# USB_Controller.net
KiCad netlist of a schematic drawn in Altium Designer
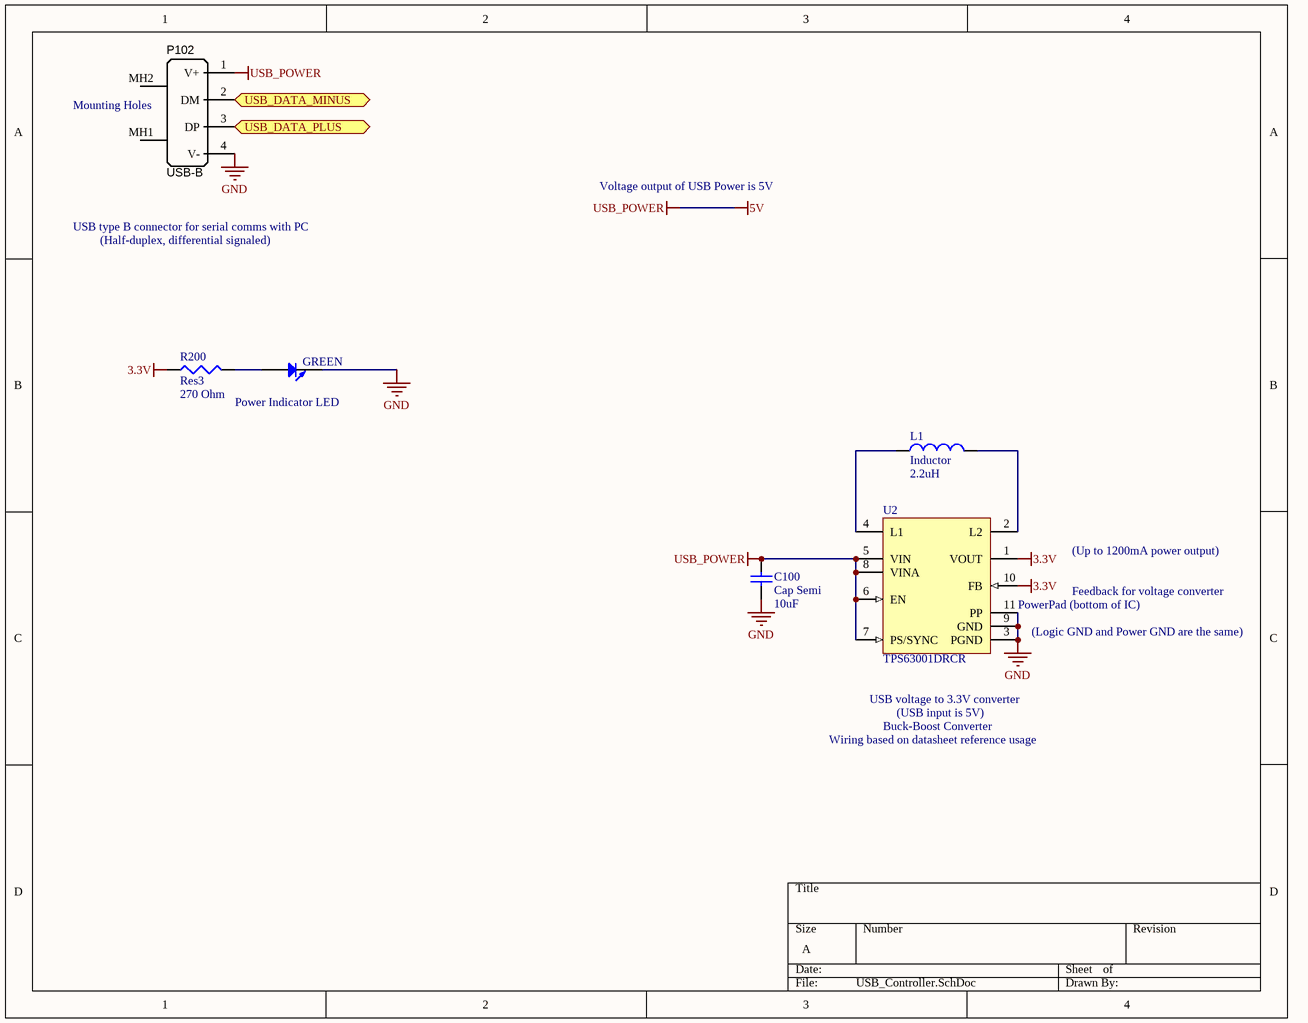
[diagram p0: USB_Controller.SchDoc]

(export (version "E")
  (design (tool "Eeschema 10.0.6"))
  (components
    (comp (ref "C100")
      (value "Cap Semi")
      (footprint "1608[0603]")
      (description "Capacitor (Semiconductor SIM Model)")
      (fields (field (name "ALTIUM_VALUE") "10uF") (field (name "PUBLISHER") "Altium Limited"))
      (libsource (lib "Miscellaneous Devices") (part "Cap Semi"))
    )
    (comp (ref "L1")
      (value "Inductor")
      (footprint "INDC3216")
      (fields (field (name "ALTIUM_VALUE") "2.2uH") (field (name "PUBLISHER") "Altium Limited"))
      (libsource (lib "Miscellaneous Devices") (part "Inductor"))
    )
    (comp (ref "LED1")
      (value "GREEN")
      (footprint "1608[0603]")
      (description "led")
      (fields
        (field (name "MANUFACTURER") "Lite-On Inc")
        (field (name "MANUFACTURER PART NUMBER") "LTST-C193KGKT-5A")
      )
      (libsource (lib "common") (part "LED0"))
    )
    (comp (ref "P102")
      (value "USB-B")
      (footprint "USB_TypeB_Tyco")
      (description "Connector THT Type B USB connector")
      (libsource (lib "PBL - Connectors") (part "USB_TypeB"))
    )
    (comp (ref "R200")
      (value "Res3")
      (footprint "1608[0603]")
      (description "Resistor")
      (fields (field (name "ALTIUM_VALUE") "270 Ohm") (field (name "PUBLISHER") "Altium Limited"))
      (libsource (lib "Miscellaneous Devices") (part "Res3"))
    )
    (comp (ref "U2")
      (value "TPS63001DRCR")
      (footprint "DRC10-2400X1650TP")
      (fields (field (name "MANUFACTURER") "Texas Instruments"))
      (libsource (lib "TI Power Management Buck-Boost Regulator") (part "TPS63001DRCR"))
    )
  )
  (nets
    (net (code "1") (name "/USB_DATA_MINUS") (class "Default")
      (node (ref "P102") (pin "2") (pinfunction "DM_2") (pintype "passive"))
    )
    (net (code "2") (name "/USB_DATA_PLUS") (class "Default")
      (node (ref "P102") (pin "3") (pinfunction "DP_3") (pintype "passive"))
    )
    (net (code "3") (name "3.3V") (class "Default")
      (node (ref "R200") (pin "1") (pinfunction "1_1") (pintype "passive"))
      (node (ref "U2") (pin "1") (pinfunction "VOUT_1") (pintype "power_in"))
      (node (ref "U2") (pin "10") (pinfunction "FB_10") (pintype "input"))
    )
    (net (code "4") (name "5V") (class "Default")
      (node (ref "C100") (pin "2") (pinfunction "2_2") (pintype "passive"))
      (node (ref "P102") (pin "1") (pinfunction "V+_1") (pintype "passive"))
      (node (ref "U2") (pin "5") (pinfunction "VIN_5") (pintype "power_in"))
      (node (ref "U2") (pin "6") (pinfunction "EN_6") (pintype "input"))
      (node (ref "U2") (pin "7") (pinfunction "PS/SYNC_7") (pintype "input"))
      (node (ref "U2") (pin "8") (pinfunction "VINA_8") (pintype "power_in"))
    )
    (net (code "5") (name "GND") (class "Default")
      (node (ref "C100") (pin "1") (pinfunction "1_1") (pintype "passive"))
      (node (ref "LED1") (pin "2") (pinfunction "K_2") (pintype "passive"))
      (node (ref "P102") (pin "4") (pinfunction "V-_4") (pintype "passive"))
      (node (ref "U2") (pin "11") (pinfunction "PP_11") (pintype "power_in"))
      (node (ref "U2") (pin "3") (pinfunction "PGND_3") (pintype "power_in"))
      (node (ref "U2") (pin "9") (pinfunction "GND_9") (pintype "power_in"))
    )
    (net (code "6") (name "Net-(LED1-A)") (class "Default")
      (node (ref "LED1") (pin "1") (pinfunction "A_1") (pintype "passive"))
      (node (ref "R200") (pin "2") (pinfunction "2_2") (pintype "passive"))
    )
    (net (code "7") (name "Net-(U2-L1)") (class "Default")
      (node (ref "L1") (pin "1") (pinfunction "1_1") (pintype "passive"))
      (node (ref "U2") (pin "4") (pinfunction "L1_4") (pintype "passive"))
    )
    (net (code "8") (name "Net-(U2-L2)") (class "Default")
      (node (ref "L1") (pin "2") (pinfunction "2_2") (pintype "passive"))
      (node (ref "U2") (pin "2") (pinfunction "L2_2") (pintype "passive"))
    )
    (net (code "9") (name "unconnected-(P102-Shell-PadMH1)") (class "Default")
      (node (ref "P102") (pin "MH1") (pinfunction "Shell_MH1") (pintype "passive"))
    )
    (net (code "10") (name "unconnected-(P102-Shell-PadMH2)") (class "Default")
      (node (ref "P102") (pin "MH2") (pinfunction "Shell_MH2") (pintype "passive"))
    )
  )
)
